# TeamB_BoatAlert.net
KiCad netlist of a schematic drawn in EAGLE
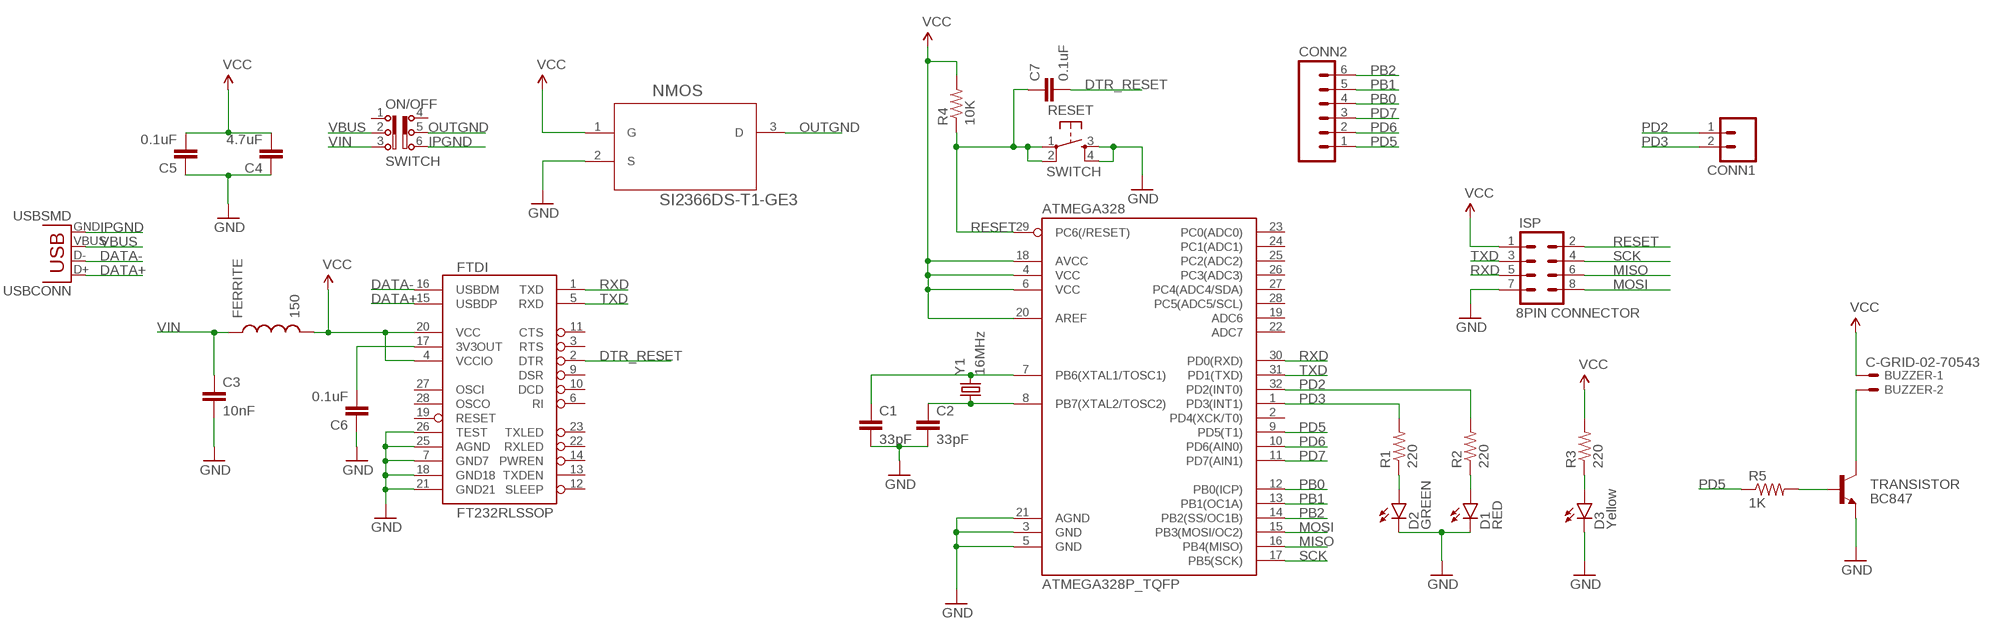
[diagram p0: schematic, sheet 1]

(export (version "E")
  (design (tool "Eeschema 10.0.6"))
  (components
    (comp (ref "ATMEGA328")
      (value "ATMEGA328P_TQFP")
      (footprint "eagle-import:TQFP32-08")
      (libsource (lib "eagle-import") (part "ATMEGA328P_TQFP"))
    )
    (comp (ref "BUZZER")
      (value "C-GRID-02-70543")
      (footprint "eagle-import:70543-02")
      (libsource (lib "eagle-import") (part "C-GRID-02-70543"))
    )
    (comp (ref "C1")
      (value "33pF")
      (footprint "eagle-import:0603-CAP")
      (libsource (lib "eagle-import") (part "33PF-50V-5%-(0603)"))
    )
    (comp (ref "C2")
      (value "33pF")
      (footprint "eagle-import:0603-CAP")
      (libsource (lib "eagle-import") (part "33PF-50V-5%-(0603)"))
    )
    (comp (ref "C3")
      (value "10nF")
      (footprint "eagle-import:0603-CAP")
      (libsource (lib "eagle-import") (part "10NF/10000PF-50V-10%(0603)"))
    )
    (comp (ref "C4")
      (value "4.7uF")
      (footprint "eagle-import:0603-CAP")
      (libsource (lib "eagle-import") (part "4.7UF-6.3V-10%(0603)0603"))
    )
    (comp (ref "C5")
      (value "0.1uF")
      (footprint "eagle-import:0603-CAP")
      (libsource (lib "eagle-import") (part "0.1UF-25V-5%(0603)"))
    )
    (comp (ref "C6")
      (value "0.1uF")
      (footprint "eagle-import:0603-CAP")
      (libsource (lib "eagle-import") (part "0.1UF-25V-5%(0603)"))
    )
    (comp (ref "C7")
      (value "0.1uF")
      (footprint "eagle-import:0603-CAP")
      (libsource (lib "eagle-import") (part "10UF-6.3V-20%(0603)"))
    )
    (comp (ref "CONN1")
      (value "M02LOCK")
      (footprint "eagle-import:1X02_LOCK")
      (libsource (lib "eagle-import") (part "M02LOCK"))
    )
    (comp (ref "CONN2")
      (value "M06LONGPADS")
      (footprint "eagle-import:1X06_LONGPADS")
      (libsource (lib "eagle-import") (part "M06LONGPADS"))
    )
    (comp (ref "D1")
      (value "RED")
      (footprint "eagle-import:LED-0603")
      (libsource (lib "eagle-import") (part "LED-RED0603"))
    )
    (comp (ref "D2")
      (value "GREEN")
      (footprint "eagle-import:LED-0603")
      (libsource (lib "eagle-import") (part "LED-GREEN0603"))
    )
    (comp (ref "D3")
      (value "Yellow")
      (footprint "eagle-import:LED-0603")
      (libsource (lib "eagle-import") (part "LED-YELLOW0603"))
    )
    (comp (ref "FERRITE")
      (value "150")
      (footprint "eagle-import:0805")
      (libsource (lib "eagle-import") (part "INDUCTOR0805"))
    )
    (comp (ref "FTDI")
      (value "FT232RLSSOP")
      (footprint "eagle-import:SSOP28DB")
      (libsource (lib "eagle-import") (part "FT232RLSSOP"))
    )
    (comp (ref "ISP")
      (value "8PIN CONNECTOR")
      (footprint "eagle-import:2X4")
      (libsource (lib "eagle-import") (part "M04X2"))
    )
    (comp (ref "NMOS")
      (value "SI2366DS-T1-GE3")
      (footprint "eagle-import:SOT95P237X112-3N")
      (libsource (lib "eagle-import") (part "SI2366DS-T1-GE3"))
    )
    (comp (ref "ON/OFF")
      (value "SWITCH")
      (footprint "eagle-import:JS202011SCQN")
      (libsource (lib "eagle-import") (part "JS202011SCQN"))
    )
    (comp (ref "R1")
      (value "220")
      (footprint "eagle-import:0805")
      (libsource (lib "eagle-import") (part "0.22OHM-1/4W-1%(0805)"))
    )
    (comp (ref "R2")
      (value "220")
      (footprint "eagle-import:0805")
      (libsource (lib "eagle-import") (part "0.22OHM-1/4W-1%(0805)"))
    )
    (comp (ref "R3")
      (value "220")
      (footprint "eagle-import:0805")
      (libsource (lib "eagle-import") (part "0.22OHM-1/4W-1%(0805)"))
    )
    (comp (ref "R4")
      (value "10K")
      (footprint "eagle-import:0603-RES")
      (libsource (lib "eagle-import") (part "10OHM-1/10W-1%(0603)SMD"))
    )
    (comp (ref "R5")
      (value "1K")
      (footprint "eagle-import:0603-RES")
      (libsource (lib "eagle-import") (part "1KOHM-1/10W-1%(0603)"))
    )
    (comp (ref "RESET")
      (value "SWITCH")
      (footprint "eagle-import:7914G")
      (libsource (lib "eagle-import") (part "TACTILE-SWITCH-7914G"))
    )
    (comp (ref "TRANSISTOR")
      (value "BC847")
      (footprint "eagle-import:SOT23-3")
      (libsource (lib "eagle-import") (part "TRANSISTOR_NPNMMBT5088"))
    )
    (comp (ref "USBCONN")
      (value "USBSMD")
      (footprint "eagle-import:USB-MINIB")
      (libsource (lib "eagle-import") (part "USBSMD"))
    )
    (comp (ref "Y1")
      (value "16MHz")
      (footprint "eagle-import:HC49UP")
      (libsource (lib "eagle-import") (part "CRYSTALSMD"))
    )
  )
  (nets
    (net (code "1") (name "/DATA+") (class "Default")
      (node (ref "FTDI") (pin "15") (pinfunction "USBDP_15") (pintype "bidirectional"))
      (node (ref "USBCONN") (pin "D+") (pinfunction "D+_D+") (pintype "bidirectional"))
    )
    (net (code "2") (name "/DATA-") (class "Default")
      (node (ref "FTDI") (pin "16") (pinfunction "USBDM_16") (pintype "bidirectional"))
      (node (ref "USBCONN") (pin "D-") (pinfunction "D-_D-") (pintype "bidirectional"))
    )
    (net (code "3") (name "/DTR_RESET") (class "Default")
      (node (ref "C7") (pin "2") (pinfunction "2_2") (pintype "passive"))
      (node (ref "FTDI") (pin "2") (pinfunction "DTR_2") (pintype "output"))
    )
    (net (code "4") (name "/IPGND") (class "Default")
      (node (ref "ON/OFF") (pin "6") (pinfunction "6_6") (pintype "passive"))
      (node (ref "USBCONN") (pin "GND") (pinfunction "GND_GND") (pintype "bidirectional"))
    )
    (net (code "5") (name "/MISO") (class "Default")
      (node (ref "ATMEGA328") (pin "16") (pinfunction "PB4(MISO)_16") (pintype "bidirectional"))
      (node (ref "ISP") (pin "6") (pinfunction "6_6") (pintype "passive"))
    )
    (net (code "6") (name "/MOSI") (class "Default")
      (node (ref "ATMEGA328") (pin "15") (pinfunction "PB3(MOSI/OC2)_15") (pintype "bidirectional"))
      (node (ref "ISP") (pin "8") (pinfunction "8_8") (pintype "passive"))
    )
    (net (code "7") (name "/OUTGND") (class "Default")
      (node (ref "NMOS") (pin "3") (pinfunction "D_3") (pintype "passive"))
      (node (ref "ON/OFF") (pin "5") (pinfunction "5_5") (pintype "passive"))
    )
    (net (code "8") (name "/PB0") (class "Default")
      (node (ref "ATMEGA328") (pin "12") (pinfunction "PB0(ICP)_12") (pintype "bidirectional"))
      (node (ref "CONN2") (pin "4") (pinfunction "4_4") (pintype "passive"))
    )
    (net (code "9") (name "/PB1") (class "Default")
      (node (ref "ATMEGA328") (pin "13") (pinfunction "PB1(OC1A)_13") (pintype "bidirectional"))
      (node (ref "CONN2") (pin "5") (pinfunction "5_5") (pintype "passive"))
    )
    (net (code "10") (name "/PB2") (class "Default")
      (node (ref "ATMEGA328") (pin "14") (pinfunction "PB2(SS/OC1B)_14") (pintype "bidirectional"))
      (node (ref "CONN2") (pin "6") (pinfunction "6_6") (pintype "passive"))
    )
    (net (code "11") (name "/PD2") (class "Default")
      (node (ref "ATMEGA328") (pin "32") (pinfunction "PD2(INT0)_32") (pintype "bidirectional"))
      (node (ref "CONN1") (pin "1") (pinfunction "1_1") (pintype "passive"))
      (node (ref "R2") (pin "2") (pinfunction "2_2") (pintype "passive"))
    )
    (net (code "12") (name "/PD3") (class "Default")
      (node (ref "ATMEGA328") (pin "1") (pinfunction "PD3(INT1)_1") (pintype "bidirectional"))
      (node (ref "CONN1") (pin "2") (pinfunction "2_2") (pintype "passive"))
      (node (ref "R1") (pin "2") (pinfunction "2_2") (pintype "passive"))
    )
    (net (code "13") (name "/PD5") (class "Default")
      (node (ref "ATMEGA328") (pin "9") (pinfunction "PD5(T1)_9") (pintype "bidirectional"))
      (node (ref "CONN2") (pin "1") (pinfunction "1_1") (pintype "passive"))
      (node (ref "R5") (pin "1") (pinfunction "1_1") (pintype "passive"))
    )
    (net (code "14") (name "/PD6") (class "Default")
      (node (ref "ATMEGA328") (pin "10") (pinfunction "PD6(AIN0)_10") (pintype "bidirectional"))
      (node (ref "CONN2") (pin "2") (pinfunction "2_2") (pintype "passive"))
    )
    (net (code "15") (name "/PD7") (class "Default")
      (node (ref "ATMEGA328") (pin "11") (pinfunction "PD7(AIN1)_11") (pintype "bidirectional"))
      (node (ref "CONN2") (pin "3") (pinfunction "3_3") (pintype "passive"))
    )
    (net (code "16") (name "/RESET") (class "Default")
      (node (ref "ATMEGA328") (pin "29") (pinfunction "PC6(/RESET)_29") (pintype "bidirectional"))
      (node (ref "C7") (pin "1") (pinfunction "1_1") (pintype "passive"))
      (node (ref "ISP") (pin "2") (pinfunction "2_2") (pintype "passive"))
      (node (ref "R4") (pin "1") (pinfunction "1_1") (pintype "passive"))
      (node (ref "RESET") (pin "1") (pinfunction "1_1") (pintype "passive"))
      (node (ref "RESET") (pin "2") (pinfunction "2_2") (pintype "passive"))
    )
    (net (code "17") (name "/RXD") (class "Default")
      (node (ref "ATMEGA328") (pin "30") (pinfunction "PD0(RXD)_30") (pintype "bidirectional"))
      (node (ref "FTDI") (pin "1") (pinfunction "TXD_1") (pintype "output"))
      (node (ref "ISP") (pin "5") (pinfunction "5_5") (pintype "passive"))
    )
    (net (code "18") (name "/SCK") (class "Default")
      (node (ref "ATMEGA328") (pin "17") (pinfunction "PB5(SCK)_17") (pintype "bidirectional"))
      (node (ref "ISP") (pin "4") (pinfunction "4_4") (pintype "passive"))
    )
    (net (code "19") (name "/TXD") (class "Default")
      (node (ref "ATMEGA328") (pin "31") (pinfunction "PD1(TXD)_31") (pintype "bidirectional"))
      (node (ref "FTDI") (pin "5") (pinfunction "RXD_5") (pintype "input"))
      (node (ref "ISP") (pin "3") (pinfunction "3_3") (pintype "passive"))
    )
    (net (code "20") (name "/VBUS") (class "Default")
      (node (ref "ON/OFF") (pin "2") (pinfunction "2_2") (pintype "passive"))
      (node (ref "USBCONN") (pin "VBUS") (pinfunction "VBUS_VBUS") (pintype "bidirectional"))
    )
    (net (code "21") (name "/VIN") (class "Default")
      (node (ref "C3") (pin "1") (pinfunction "1_1") (pintype "passive"))
      (node (ref "FERRITE") (pin "1") (pinfunction "1_1") (pintype "passive"))
      (node (ref "ON/OFF") (pin "3") (pinfunction "3_3") (pintype "passive"))
    )
    (net (code "22") (name "GND") (class "Default")
      (node (ref "ATMEGA328") (pin "21") (pinfunction "AGND_21") (pintype "bidirectional"))
      (node (ref "ATMEGA328") (pin "3") (pinfunction "GND_3") (pintype "bidirectional"))
      (node (ref "ATMEGA328") (pin "5") (pinfunction "GND_5") (pintype "bidirectional"))
      (node (ref "C1") (pin "2") (pinfunction "2_2") (pintype "passive"))
      (node (ref "C2") (pin "2") (pinfunction "2_2") (pintype "passive"))
      (node (ref "C3") (pin "2") (pinfunction "2_2") (pintype "passive"))
      (node (ref "C4") (pin "1") (pinfunction "1_1") (pintype "passive"))
      (node (ref "C5") (pin "1") (pinfunction "1_1") (pintype "passive"))
      (node (ref "C6") (pin "1") (pinfunction "1_1") (pintype "passive"))
      (node (ref "D1") (pin "C") (pinfunction "C_C") (pintype "passive"))
      (node (ref "D2") (pin "C") (pinfunction "C_C") (pintype "passive"))
      (node (ref "D3") (pin "C") (pinfunction "C_C") (pintype "passive"))
      (node (ref "FTDI") (pin "18") (pinfunction "GND18_18") (pintype "power_in"))
      (node (ref "FTDI") (pin "21") (pinfunction "GND21_21") (pintype "power_in"))
      (node (ref "FTDI") (pin "25") (pinfunction "AGND_25") (pintype "power_in"))
      (node (ref "FTDI") (pin "26") (pinfunction "TEST_26") (pintype "input"))
      (node (ref "FTDI") (pin "7") (pinfunction "GND7_7") (pintype "power_in"))
      (node (ref "ISP") (pin "7") (pinfunction "7_7") (pintype "passive"))
      (node (ref "NMOS") (pin "2") (pinfunction "S_2") (pintype "passive"))
      (node (ref "RESET") (pin "3") (pinfunction "3_3") (pintype "passive"))
      (node (ref "RESET") (pin "4") (pinfunction "4_4") (pintype "passive"))
      (node (ref "TRANSISTOR") (pin "2") (pinfunction "E_2") (pintype "passive"))
    )
    (net (code "23") (name "Net-(ATMEGA328-PB6(XTAL1{slash}TOSC1))") (class "Default")
      (node (ref "ATMEGA328") (pin "7") (pinfunction "PB6(XTAL1/TOSC1)_7") (pintype "bidirectional"))
      (node (ref "C1") (pin "1") (pinfunction "1_1") (pintype "passive"))
      (node (ref "Y1") (pin "2") (pinfunction "2_2") (pintype "passive"))
    )
    (net (code "24") (name "Net-(ATMEGA328-PB7(XTAL2{slash}TOSC2))") (class "Default")
      (node (ref "ATMEGA328") (pin "8") (pinfunction "PB7(XTAL2/TOSC2)_8") (pintype "bidirectional"))
      (node (ref "C2") (pin "1") (pinfunction "1_1") (pintype "passive"))
      (node (ref "Y1") (pin "1") (pinfunction "1_1") (pintype "passive"))
    )
    (net (code "25") (name "Net-(BUZZERB-S)") (class "Default")
      (node (ref "BUZZER") (pin "2") (pinfunction "S_2") (pintype "passive"))
      (node (ref "TRANSISTOR") (pin "3") (pinfunction "C_3") (pintype "passive"))
    )
    (net (code "26") (name "Net-(D1-PadA)") (class "Default")
      (node (ref "D1") (pin "A") (pinfunction "A_A") (pintype "passive"))
      (node (ref "R2") (pin "1") (pinfunction "1_1") (pintype "passive"))
    )
    (net (code "27") (name "Net-(D2-PadA)") (class "Default")
      (node (ref "D2") (pin "A") (pinfunction "A_A") (pintype "passive"))
      (node (ref "R1") (pin "1") (pinfunction "1_1") (pintype "passive"))
    )
    (net (code "28") (name "Net-(D3-PadA)") (class "Default")
      (node (ref "D3") (pin "A") (pinfunction "A_A") (pintype "passive"))
      (node (ref "R3") (pin "1") (pinfunction "1_1") (pintype "passive"))
    )
    (net (code "29") (name "Net-(FTDI-3V3OUT)") (class "Default")
      (node (ref "C6") (pin "2") (pinfunction "2_2") (pintype "passive"))
      (node (ref "FTDI") (pin "17") (pinfunction "3V3OUT_17") (pintype "output"))
    )
    (net (code "30") (name "Net-(TRANSISTOR-B)") (class "Default")
      (node (ref "R5") (pin "2") (pinfunction "2_2") (pintype "passive"))
      (node (ref "TRANSISTOR") (pin "1") (pinfunction "B_1") (pintype "passive"))
    )
    (net (code "31") (name "VCC") (class "Default")
      (node (ref "ATMEGA328") (pin "18") (pinfunction "AVCC_18") (pintype "bidirectional"))
      (node (ref "ATMEGA328") (pin "20") (pinfunction "AREF_20") (pintype "bidirectional"))
      (node (ref "ATMEGA328") (pin "4") (pinfunction "VCC_4") (pintype "bidirectional"))
      (node (ref "ATMEGA328") (pin "6") (pinfunction "VCC_6") (pintype "bidirectional"))
      (node (ref "BUZZER") (pin "1") (pinfunction "S_1") (pintype "passive"))
      (node (ref "C4") (pin "2") (pinfunction "2_2") (pintype "passive"))
      (node (ref "C5") (pin "2") (pinfunction "2_2") (pintype "passive"))
      (node (ref "FERRITE") (pin "2") (pinfunction "2_2") (pintype "passive"))
      (node (ref "FTDI") (pin "20") (pinfunction "VCC_20") (pintype "power_in"))
      (node (ref "FTDI") (pin "4") (pinfunction "VCCIO_4") (pintype "power_in"))
      (node (ref "ISP") (pin "1") (pinfunction "1_1") (pintype "passive"))
      (node (ref "NMOS") (pin "1") (pinfunction "G_1") (pintype "passive"))
      (node (ref "R3") (pin "2") (pinfunction "2_2") (pintype "passive"))
      (node (ref "R4") (pin "2") (pinfunction "2_2") (pintype "passive"))
    )
    (net (code "32") (name "unconnected-(ATMEGA328-ADC6-Pad19)") (class "Default")
      (node (ref "ATMEGA328") (pin "19") (pinfunction "ADC6_19") (pintype "bidirectional"))
    )
    (net (code "33") (name "unconnected-(ATMEGA328-ADC7-Pad22)") (class "Default")
      (node (ref "ATMEGA328") (pin "22") (pinfunction "ADC7_22") (pintype "bidirectional"))
    )
    (net (code "34") (name "unconnected-(ATMEGA328-PC0(ADC0)-Pad23)") (class "Default")
      (node (ref "ATMEGA328") (pin "23") (pinfunction "PC0(ADC0)_23") (pintype "bidirectional"))
    )
    (net (code "35") (name "unconnected-(ATMEGA328-PC1(ADC1)-Pad24)") (class "Default")
      (node (ref "ATMEGA328") (pin "24") (pinfunction "PC1(ADC1)_24") (pintype "bidirectional"))
    )
    (net (code "36") (name "unconnected-(ATMEGA328-PC2(ADC2)-Pad25)") (class "Default")
      (node (ref "ATMEGA328") (pin "25") (pinfunction "PC2(ADC2)_25") (pintype "bidirectional"))
    )
    (net (code "37") (name "unconnected-(ATMEGA328-PC3(ADC3)-Pad26)") (class "Default")
      (node (ref "ATMEGA328") (pin "26") (pinfunction "PC3(ADC3)_26") (pintype "bidirectional"))
    )
    (net (code "38") (name "unconnected-(ATMEGA328-PC4(ADC4{slash}SDA)-Pad27)") (class "Default")
      (node (ref "ATMEGA328") (pin "27") (pinfunction "PC4(ADC4/SDA)_27") (pintype "bidirectional"))
    )
    (net (code "39") (name "unconnected-(ATMEGA328-PC5(ADC5{slash}SCL)-Pad28)") (class "Default")
      (node (ref "ATMEGA328") (pin "28") (pinfunction "PC5(ADC5/SCL)_28") (pintype "bidirectional"))
    )
    (net (code "40") (name "unconnected-(ATMEGA328-PD4(XCK{slash}T0)-Pad2)") (class "Default")
      (node (ref "ATMEGA328") (pin "2") (pinfunction "PD4(XCK/T0)_2") (pintype "bidirectional"))
    )
    (net (code "41") (name "unconnected-(FTDI-CTS-Pad11)") (class "Default")
      (node (ref "FTDI") (pin "11") (pinfunction "CTS_11") (pintype "input"))
    )
    (net (code "42") (name "unconnected-(FTDI-DCD-Pad10)") (class "Default")
      (node (ref "FTDI") (pin "10") (pinfunction "DCD_10") (pintype "input"))
    )
    (net (code "43") (name "unconnected-(FTDI-DSR-Pad9)") (class "Default")
      (node (ref "FTDI") (pin "9") (pinfunction "DSR_9") (pintype "input"))
    )
    (net (code "44") (name "unconnected-(FTDI-OSCI-Pad27)") (class "Default")
      (node (ref "FTDI") (pin "27") (pinfunction "OSCI_27") (pintype "input"))
    )
    (net (code "45") (name "unconnected-(FTDI-OSCO-Pad28)") (class "Default")
      (node (ref "FTDI") (pin "28") (pinfunction "OSCO_28") (pintype "output"))
    )
    (net (code "46") (name "unconnected-(FTDI-PWREN-Pad14)") (class "Default")
      (node (ref "FTDI") (pin "14") (pinfunction "PWREN_14") (pintype "input"))
    )
    (net (code "47") (name "unconnected-(FTDI-RESET-Pad19)") (class "Default")
      (node (ref "FTDI") (pin "19") (pinfunction "RESET_19") (pintype "input"))
    )
    (net (code "48") (name "unconnected-(FTDI-RI-Pad6)") (class "Default")
      (node (ref "FTDI") (pin "6") (pinfunction "RI_6") (pintype "input"))
    )
    (net (code "49") (name "unconnected-(FTDI-RTS-Pad3)") (class "Default")
      (node (ref "FTDI") (pin "3") (pinfunction "RTS_3") (pintype "output"))
    )
    (net (code "50") (name "unconnected-(FTDI-RXLED-Pad22)") (class "Default")
      (node (ref "FTDI") (pin "22") (pinfunction "RXLED_22") (pintype "input"))
    )
    (net (code "51") (name "unconnected-(FTDI-SLEEP-Pad12)") (class "Default")
      (node (ref "FTDI") (pin "12") (pinfunction "SLEEP_12") (pintype "input"))
    )
    (net (code "52") (name "unconnected-(FTDI-TXDEN-Pad13)") (class "Default")
      (node (ref "FTDI") (pin "13") (pinfunction "TXDEN_13") (pintype "input"))
    )
    (net (code "53") (name "unconnected-(FTDI-TXLED-Pad23)") (class "Default")
      (node (ref "FTDI") (pin "23") (pinfunction "TXLED_23") (pintype "input"))
    )
    (net (code "54") (name "unconnected-(ON/OFF-Pad1)") (class "Default")
      (node (ref "ON/OFF") (pin "1") (pinfunction "1_1") (pintype "passive"))
    )
    (net (code "55") (name "unconnected-(ON/OFF-Pad4)") (class "Default")
      (node (ref "ON/OFF") (pin "4") (pinfunction "4_4") (pintype "passive"))
    )
  )
)
